# MelansonTech_Isolated_Shunt_Amplifier.net
KiCad netlist of a schematic drawn in Altium Designer
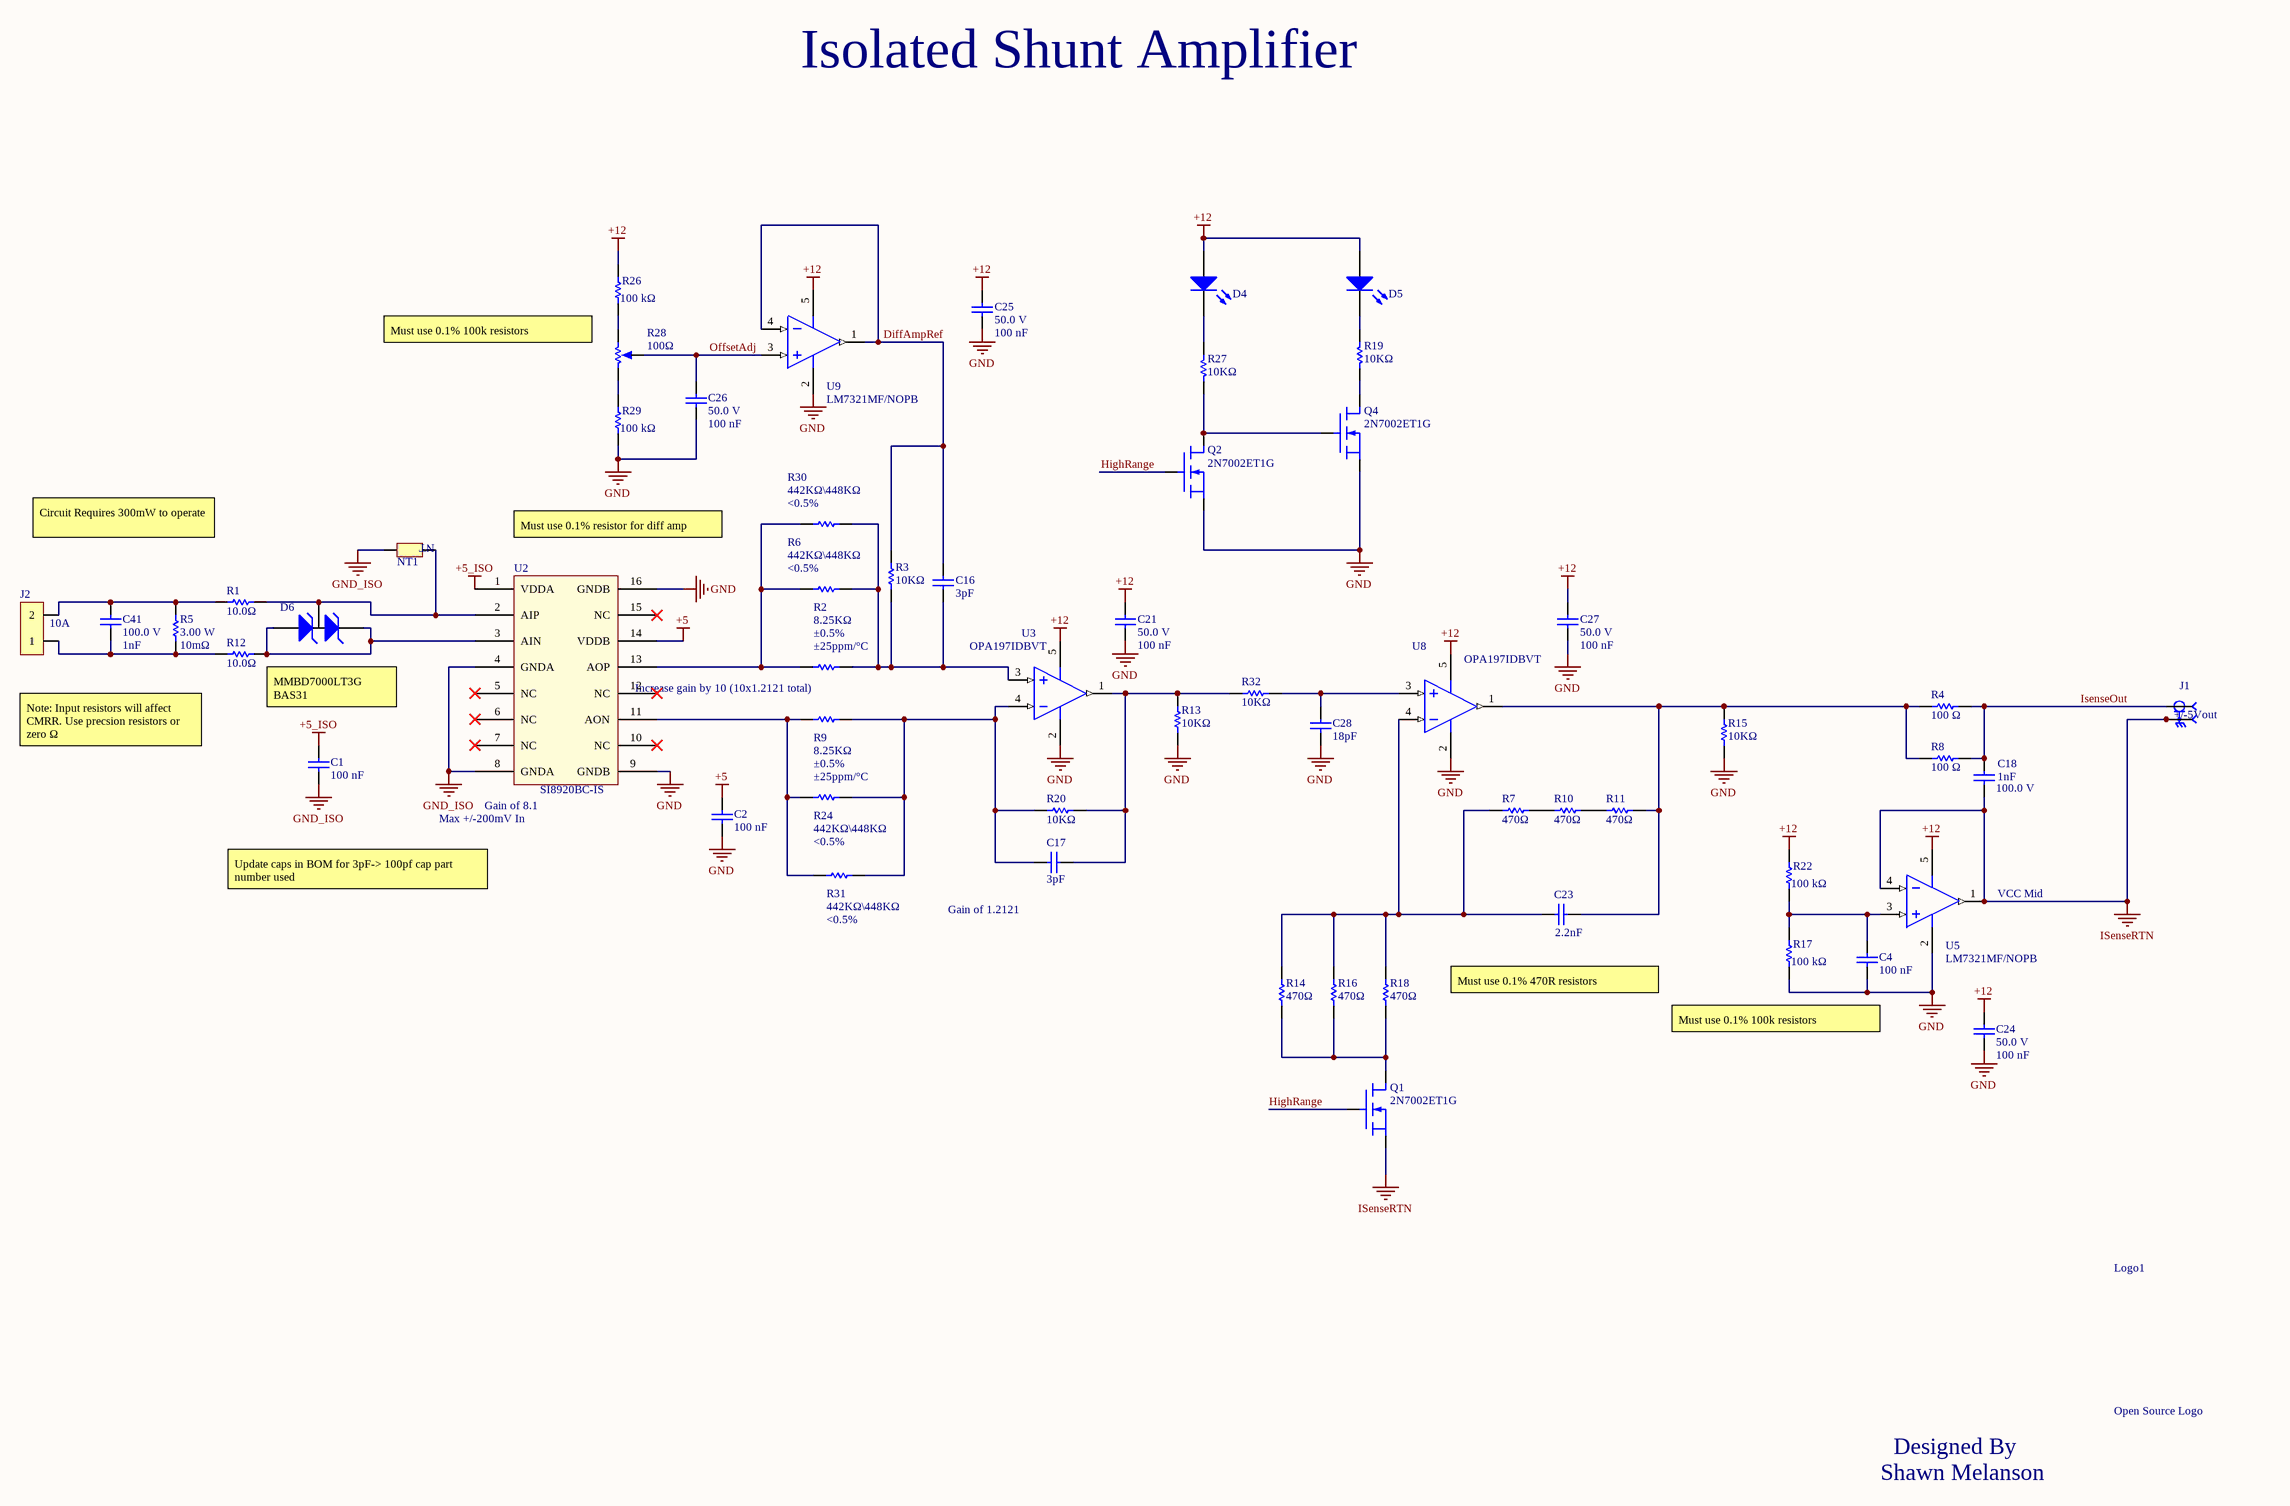
[diagram p0: MelansonTech Isolated Shunt Amplifier.SchDoc]

(export (version "E")
  (design (tool "Eeschema 10.0.6"))
  (components
    (comp (ref "C1")
      (value "08055C104JAT2A")
      (footprint "CAP, 0805, HD")
      (description "Capacitor; Ceramic; Cap 0.1 uF; Tol 5%; Vol-Rtg 50 VDC; SMT; 0805; X7R; Tape & Reel")
      (fields (field (name "CAPACITANCE") "100 nF"))
      (libsource (lib "Master Oct28_2018") (part "Cap,0805,100nf,50V,5%,08055C104JAT2A"))
    )
    (comp (ref "C2")
      (value "08055C104JAT2A")
      (footprint "CAP, 0805, HD")
      (description "Capacitor; Ceramic; Cap 0.1 uF; Tol 5%; Vol-Rtg 50 VDC; SMT; 0805; X7R; Tape & Reel")
      (fields (field (name "CAPACITANCE") "100 nF"))
      (libsource (lib "Master Oct28_2018") (part "Cap,0805,100nf,50V,5%,08055C104JAT2A"))
    )
    (comp (ref "C4")
      (value "08055C104JAT2A")
      (footprint "CAP, 0805, HD")
      (description "Capacitor; Ceramic; Cap 0.1 uF; Tol 5%; Vol-Rtg 50 VDC; SMT; 0805; X7R; Tape & Reel")
      (fields (field (name "CAPACITANCE") "100 nF"))
      (libsource (lib "Master Oct28_2018") (part "Cap,0805,100nf,50V,5%,08055C104JAT2A"))
    )
    (comp (ref "C16")
      (value "GRM21A5C2E101JW01D")
      (footprint "CAP, 0805, HD")
      (fields (field (name "CAPACITANCE") "3pF"))
      (libsource (lib "Master Nov2021") (part "CAP,0805,Generic"))
    )
    (comp (ref "C17")
      (value "GRM21A5C2E101JW01D")
      (footprint "CAP, 0805, HD")
      (fields (field (name "CAPACITANCE") "3pF"))
      (libsource (lib "Master Nov2021") (part "CAP,0805,Generic"))
    )
    (comp (ref "C18")
      (value "C0805X102J1GACAUTO")
      (footprint "CAP, 0805, HD")
      (description "CAPACITOR, 1NF, 100V, NP0, 0805")
      (fields (field (name "VOLTAGE RATING (DC)") "100.0 V") (field (name "CAPACITANCE") "1nF"))
      (libsource (lib "Master Nov2021") (part "Cap,0805,1nF,±5%,100Vdc,CL10F104ZB8NNNC"))
    )
    (comp (ref "C21")
      (value "08055C104JAT2A")
      (footprint "CAP, 0805, HD")
      (description "Capacitor; Ceramic; Cap 0.1 uF; Tol 5%; Vol-Rtg 50 VDC; SMT; 0805; X7R; Tape & Reel")
      (fields (field (name "VOLTAGE RATING (DC)") "50.0 V") (field (name "CAPACITANCE") "100 nF"))
      (libsource (lib "Master Mar2021") (part "Cap,0805,100nf,50V,5%,08055C104JAT2A"))
    )
    (comp (ref "C23")
      (value "Cap")
      (footprint "CAP, 0805, HD")
      (fields (field (name "CAP") "2.2nF"))
      (libsource (lib "Master Nov2021") (part "CAP,0805,Generic"))
    )
    (comp (ref "C24")
      (value "08055C104JAT2A")
      (footprint "CAP, 0805, HD")
      (description "Capacitor; Ceramic; Cap 0.1 uF; Tol 5%; Vol-Rtg 50 VDC; SMT; 0805; X7R; Tape & Reel")
      (fields (field (name "VOLTAGE RATING (DC)") "50.0 V") (field (name "CAPACITANCE") "100 nF"))
      (libsource (lib "Master Mar2021") (part "Cap,0805,100nf,50V,5%,08055C104JAT2A"))
    )
    (comp (ref "C25")
      (value "08055C104JAT2A")
      (footprint "CAP, 0805, HD")
      (description "Capacitor; Ceramic; Cap 0.1 uF; Tol 5%; Vol-Rtg 50 VDC; SMT; 0805; X7R; Tape & Reel")
      (fields (field (name "VOLTAGE RATING (DC)") "50.0 V") (field (name "CAPACITANCE") "100 nF"))
      (libsource (lib "Master Mar2021") (part "Cap,0805,100nf,50V,5%,08055C104JAT2A"))
    )
    (comp (ref "C26")
      (value "08055C104JAT2A")
      (footprint "CAP, 0805, HD")
      (description "Capacitor; Ceramic; Cap 0.1 uF; Tol 5%; Vol-Rtg 50 VDC; SMT; 0805; X7R; Tape & Reel")
      (fields (field (name "VOLTAGE RATING (DC)") "50.0 V") (field (name "CAPACITANCE") "100 nF"))
      (libsource (lib "Master Mar2021") (part "Cap,0805,100nf,50V,5%,08055C104JAT2A"))
    )
    (comp (ref "C27")
      (value "08055C104JAT2A")
      (footprint "CAP, 0805, HD")
      (description "Capacitor; Ceramic; Cap 0.1 uF; Tol 5%; Vol-Rtg 50 VDC; SMT; 0805; X7R; Tape & Reel")
      (fields (field (name "VOLTAGE RATING (DC)") "50.0 V") (field (name "CAPACITANCE") "100 nF"))
      (libsource (lib "Master Mar2021") (part "Cap,0805,100nf,50V,5%,08055C104JAT2A"))
    )
    (comp (ref "C28")
      (value "GRM21A5C2E101JW01D")
      (footprint "CAP, 0805, HD")
      (fields (field (name "CAPACITANCE") "18pF"))
      (libsource (lib "Master Nov2021") (part "CAP,0805,Generic"))
    )
    (comp (ref "C41")
      (value "C0805X102J1GACAUTO")
      (footprint "CAP, 0805, HD")
      (description "CAPACITOR, 1NF, 100V, NP0, 0805")
      (fields (field (name "VOLTAGE RATING (DC)") "100.0 V") (field (name "CAPACITANCE") "1nF"))
      (libsource (lib "Master Nov2021") (part "Cap,0805,1nF,±5%,100Vdc,CL10F104ZB8NNNC"))
    )
    (comp (ref "D4")
      (value "OVLBB4C7")
      (footprint "LED,TH,T1,3MM-Vert")
      (description "Blue 470nm LED Indication - Discrete 3.2V Radial")
      (fields (field (name "MFG") "TT Electronics/Optek Technology"))
      (libsource (lib "Master Nov2021") (part "LED,TH,T1,3mm,Blue,OVLBB4C7"))
    )
    (comp (ref "D5")
      (value "OVLBB4C7")
      (footprint "LED,TH,T1,3MM-Vert")
      (description "Blue 470nm LED Indication - Discrete 3.2V Radial")
      (fields (field (name "MFG") "TT Electronics/Optek Technology"))
      (libsource (lib "Master Nov2021") (part "LED,TH,T1,3mm,Blue,OVLBB4C7"))
    )
    (comp (ref "D6")
      (value "BAT54SLT1G")
      (footprint "SOT23-3")
      (fields (field (name "BASE PART NUMBER") "BAT54SL") (field (name "MANUFACTURER") "ON Semiconductor"))
      (libsource (lib "Master Nov2021") (part "Diode,Shottky,Array,Series,30V,200mA,BAT54SLT1G"))
    )
    (comp (ref "J1")
      (value "142-0701-801")
      (footprint "CINCH_142-0701-801")
      (description "CONN SMA JACK STR 50OHM EDGE MNT")
      (fields (field (name "MANUFACTURER") "Cinch Connectivity Solutions Johnson"))
      (libsource (lib "Master JUL_2019-Shawn") (part "Conn,SMA,Female,End Launch,142-0701-801"))
    )
    (comp (ref "J2")
      (value "TE Connectivity 282836-2")
      (footprint "TERM BLOCK 2POS SIDE ENTRY 5MM")
      (description "Wire to Board 2 Position 5 mm Pitch 30-16 AWG Euro Style Terminal Block")
      (fields (field (name "MANUFACTURER PART NUMBER") "282836-2"))
      (libsource (lib "Master DEC 2020") (part "TERM BLOCK 2POS SIDE ENTRY 5MM, 282836-2"))
    )
    (comp (ref "Logo1")
      (value "Open Source Logo")
      (footprint "Symbol,Open Source - No Text")
      (description "Open Source Silk Screen Logo")
      (libsource (lib "Master Nov2021") (part "Symbol,Open Source"))
    )
    (comp (ref "NT1")
      (value "Net Tie,0.254mm")
      (footprint "0.254mm Net Tie")
      (libsource (lib "Master Mar2021") (part "Net Tie,0.254mm"))
    )
    (comp (ref "Q1")
      (value "2N7002ET1G")
      (footprint "SOT23-3")
      (description "Small Signal MOSFET, 60 V, 310 mA, Single, N-Channel, 3-Pin SOT-23, Pb-Free, Tape and Reel")
      (fields
        (field (name "MANUFACTURER") "ON Semiconductor")
        (field (name "MANUFACTURER PART NUMBER") "2N7002ET1G")
      )
      (libsource (lib "Master DEC 2020") (part "MOSFET,N-Channel,SOT23,0.25A,60V,2N7002ET1G"))
    )
    (comp (ref "Q2")
      (value "2N7002ET1G")
      (footprint "SOT23-3")
      (description "Small Signal MOSFET, 60 V, 310 mA, Single, N-Channel, 3-Pin SOT-23, Pb-Free, Tape and Reel")
      (fields
        (field (name "MANUFACTURER") "ON Semiconductor")
        (field (name "MANUFACTURER PART NUMBER") "2N7002ET1G")
      )
      (libsource (lib "Master DEC 2020") (part "MOSFET,N-Channel,SOT23,0.25A,60V,2N7002ET1G"))
    )
    (comp (ref "Q4")
      (value "2N7002ET1G")
      (footprint "SOT23-3")
      (description "Small Signal MOSFET, 60 V, 310 mA, Single, N-Channel, 3-Pin SOT-23, Pb-Free, Tape and Reel")
      (fields
        (field (name "MANUFACTURER") "ON Semiconductor")
        (field (name "MANUFACTURER PART NUMBER") "2N7002ET1G")
      )
      (libsource (lib "Master DEC 2020") (part "MOSFET,N-Channel,SOT23,0.25A,60V,2N7002ET1G"))
    )
    (comp (ref "R1")
      (value "Vishay CRCW08051K00JNEA")
      (footprint "res, 0805, HD")
      (description "RES 10 OHM 5% 1/8W 0805")
      (fields
        (field (name "MANUFACTURER") "Stackpole Electronics Inc")
        (field (name "TOLERANCE") "±5%")
        (field (name "RESISTANCE") "10.0Ω")
      )
      (libsource (lib "Master Nov2021") (part "Res,0805,10.0Ω,5%,±200ppm/°C,RMCF0805JT10R0"))
    )
    (comp (ref "R2")
      (value "RR1220P-8251-D-M")
      (footprint "res, 0805, HD")
      (description "RES SMD 8.25KOHM 0.5% 1/10W 0805")
      (fields
        (field (name "MANUFACTURER") "Susumu")
        (field (name "TOLERANCE") "±0.5%")
        (field (name "TEMPERATURE COEFFICIENT") "±25ppm/°C")
        (field (name "RESISTANCE") "8.25KΩ")
      )
      (libsource (lib "Master DEC 2020") (part "Res,0805,8.25KΩ,0.5%,±25ppm/°C,RR1220P-8251-D-M"))
    )
    (comp (ref "R3")
      (value "Vishay / Dale CRCW080510K0FKTA")
      (footprint "res, 0805, HD")
      (description "RES SMD 10K OHM 1% 1/8W 0805")
      (fields (field (name "RESISTANCE") "10KΩ"))
      (libsource (lib "Master DEC 2020") (part "Res,0805,10.0kΩ,1%,100 ppm,CRCW080510K0FKTA"))
    )
    (comp (ref "R4")
      (value "CRCW0805100RJNEAC")
      (footprint "res, 0805, HD")
      (description "RES 100 OHM 5% 1/8W 0805")
      (fields (field (name "TOLERANCE") "±5%") (field (name "RESISTANCE") "100 Ω"))
      (libsource (lib "Master DEC 2020") (part "Res,0805,100Ω,5%,±200ppm/°C"))
    )
    (comp (ref "R5")
      (value "Res1")
      (footprint "Res 2512")
      (description "Resistor; Metal Film; Res 0.01 Ohms; Pwr-Rtg 3 W; Tol 1%; SMT; 2512; Current Sense")
      (fields
        (field (name "MANUFACTURER PART NUMBER") "CRA2512-FZ-R010ELF")
        (field (name "POWER RATING") "3.00 W")
        (field (name "RESISTANCE") "10mΩ")
      )
      (libsource (lib "Master JULY2019") (part "Res,2512,10mΩ,3.00W,±1%,CRA2512-FZ-R010ELF"))
    )
    (comp (ref "R6")
      (value "~")
      (footprint "res, 0805, HD")
      (fields (field (name "RESISTANCE") "442KΩ\\448KΩ") (field (name "TOLERANCE") "<0.5%"))
      (libsource (lib "Master Nov2021") (part "Res,0805,Generic"))
    )
    (comp (ref "R7")
      (value "CR0805-JW-471ELF")
      (footprint "res, 0805, HD")
      (description "RES SMD 470 OHM 5% 1/8W 0805")
      (fields
        (field (name "MANUFACTURER") "Bourns Inc.")
        (field (name "TOLERANCE") "±5%")
        (field (name "RESISTANCE") "470Ω")
      )
      (libsource (lib "Master Nov2021") (part "res,0805,470Ω,5%,200ppm,CR0805-JW-471ELF"))
    )
    (comp (ref "R8")
      (value "CRCW0805100RJNEAC")
      (footprint "res, 0805, HD")
      (description "RES 100 OHM 5% 1/8W 0805")
      (fields (field (name "TOLERANCE") "±5%") (field (name "RESISTANCE") "100 Ω"))
      (libsource (lib "Master DEC 2020") (part "Res,0805,100Ω,5%,±200ppm/°C"))
    )
    (comp (ref "R9")
      (value "RR1220P-8251-D-M")
      (footprint "res, 0805, HD")
      (description "RES SMD 8.25KOHM 0.5% 1/10W 0805")
      (fields
        (field (name "MANUFACTURER") "Susumu")
        (field (name "TOLERANCE") "±0.5%")
        (field (name "TEMPERATURE COEFFICIENT") "±25ppm/°C")
        (field (name "RESISTANCE") "8.25KΩ")
      )
      (libsource (lib "Master DEC 2020") (part "Res,0805,8.25KΩ,0.5%,±25ppm/°C,RR1220P-8251-D-M"))
    )
    (comp (ref "R10")
      (value "CR0805-JW-471ELF")
      (footprint "res, 0805, HD")
      (description "RES SMD 470 OHM 5% 1/8W 0805")
      (fields
        (field (name "MANUFACTURER") "Bourns Inc.")
        (field (name "TOLERANCE") "±5%")
        (field (name "RESISTANCE") "470Ω")
      )
      (libsource (lib "Master Nov2021") (part "res,0805,470Ω,5%,200ppm,CR0805-JW-471ELF"))
    )
    (comp (ref "R11")
      (value "CR0805-JW-471ELF")
      (footprint "res, 0805, HD")
      (description "RES SMD 470 OHM 5% 1/8W 0805")
      (fields
        (field (name "MANUFACTURER") "Bourns Inc.")
        (field (name "TOLERANCE") "±5%")
        (field (name "RESISTANCE") "470Ω")
      )
      (libsource (lib "Master Nov2021") (part "res,0805,470Ω,5%,200ppm,CR0805-JW-471ELF"))
    )
    (comp (ref "R12")
      (value "Vishay / Dale CRCW080510K0FKTA")
      (footprint "res, 0805, HD")
      (description "RES 10 OHM 5% 1/8W 0805")
      (fields
        (field (name "MANUFACTURER") "Stackpole Electronics Inc")
        (field (name "TOLERANCE") "±5%")
        (field (name "RESISTANCE") "10.0Ω")
      )
      (libsource (lib "Master Nov2021") (part "Res,0805,10.0Ω,5%,±200ppm/°C,RMCF0805JT10R0"))
    )
    (comp (ref "R13")
      (value "Vishay / Dale CRCW080510K0FKTA")
      (footprint "res, 0805, HD")
      (description "RES SMD 10K OHM 1% 1/8W 0805")
      (fields (field (name "RESISTANCE") "10KΩ"))
      (libsource (lib "Master DEC 2020") (part "Res,0805,10.0kΩ,1%,100 ppm,CRCW080510K0FKTA"))
    )
    (comp (ref "R14")
      (value "CR0805-JW-471ELF")
      (footprint "res, 0805, HD")
      (description "RES SMD 470 OHM 5% 1/8W 0805")
      (fields
        (field (name "MANUFACTURER") "Bourns Inc.")
        (field (name "TOLERANCE") "±5%")
        (field (name "RESISTANCE") "470Ω")
      )
      (libsource (lib "Master Nov2021") (part "res,0805,470Ω,5%,200ppm,CR0805-JW-471ELF"))
    )
    (comp (ref "R15")
      (value "Vishay / Dale CRCW080510K0FKTA")
      (footprint "res, 0805, HD")
      (description "RES SMD 10K OHM 1% 1/8W 0805")
      (fields (field (name "RESISTANCE") "10KΩ"))
      (libsource (lib "Master JULY2019") (part "Res,0805,10.0kΩ,1%,100 ppm,CRCW080510K0FKTA"))
    )
    (comp (ref "R16")
      (value "CR0805-JW-471ELF")
      (footprint "res, 0805, HD")
      (description "RES SMD 470 OHM 5% 1/8W 0805")
      (fields
        (field (name "MANUFACTURER") "Bourns Inc.")
        (field (name "TOLERANCE") "±5%")
        (field (name "RESISTANCE") "470Ω")
      )
      (libsource (lib "Master Nov2021") (part "res,0805,470Ω,5%,200ppm,CR0805-JW-471ELF"))
    )
    (comp (ref "R17")
      (value "CRCW0805100KFKEA")
      (footprint "res, 0805, HD")
      (description "100 kOhms ±1% 0.125W, 1/8W Chip Resistor 0805 (2012 Metric) Thick Film")
      (fields (field (name "MANUFACTURER") "Vishay") (field (name "RESISTANCE") "100 kΩ"))
      (libsource (lib "Master Nov2021") (part "Res,0805,100kΩ,1%,100ppm,CRCW0805100KFKEA"))
    )
    (comp (ref "R18")
      (value "CR0805-JW-471ELF")
      (footprint "res, 0805, HD")
      (description "RES SMD 470 OHM 5% 1/8W 0805")
      (fields
        (field (name "MANUFACTURER") "Bourns Inc.")
        (field (name "TOLERANCE") "±5%")
        (field (name "RESISTANCE") "470Ω")
      )
      (libsource (lib "Master Nov2021") (part "res,0805,470Ω,5%,200ppm,CR0805-JW-471ELF"))
    )
    (comp (ref "R19")
      (value "Vishay / Dale CRCW080510K0FKTA")
      (footprint "res, 0805, HD")
      (description "RES SMD 10K OHM 1% 1/8W 0805")
      (fields (field (name "RESISTANCE") "10KΩ"))
      (libsource (lib "Master JULY2019") (part "Res,0805,10.0kΩ,1%,100 ppm,CRCW080510K0FKTA"))
    )
    (comp (ref "R20")
      (value "Vishay / Dale CRCW080510K0FKTA")
      (footprint "res, 0805, HD")
      (description "RES SMD 10K OHM 1% 1/8W 0805")
      (fields (field (name "RESISTANCE") "10KΩ"))
      (libsource (lib "Master Nov2021") (part "Res,0805,10.0kΩ,1%,100 ppm,CRCW080510K0FKTA"))
    )
    (comp (ref "R22")
      (value "CRCW0805100KFKEA")
      (footprint "res, 0805, HD")
      (description "100 kOhms ±1% 0.125W, 1/8W Chip Resistor 0805 (2012 Metric) Thick Film")
      (fields (field (name "MANUFACTURER") "Vishay") (field (name "RESISTANCE") "100 kΩ"))
      (libsource (lib "Master Nov2021") (part "Res,0805,100kΩ,1%,100ppm,CRCW0805100KFKEA"))
    )
    (comp (ref "R24")
      (value "~")
      (footprint "res, 0805, HD")
      (fields (field (name "RESISTANCE") "442KΩ\\448KΩ") (field (name "TOLERANCE") "<0.5%"))
      (libsource (lib "Master Nov2021") (part "Res,0805,Generic"))
    )
    (comp (ref "R26")
      (value "CRCW0805100KFKEA")
      (footprint "res, 0805, HD")
      (description "100 kOhms ±1% 0.125W, 1/8W Chip Resistor 0805 (2012 Metric) Thick Film")
      (fields (field (name "MANUFACTURER") "Vishay") (field (name "RESISTANCE") "100 kΩ"))
      (libsource (lib "Master Nov2021") (part "Res,0805,100kΩ,1%,100ppm,CRCW0805100KFKEA"))
    )
    (comp (ref "R27")
      (value "Vishay / Dale CRCW080510K0FKTA")
      (footprint "res, 0805, HD")
      (description "RES SMD 10K OHM 1% 1/8W 0805")
      (fields (field (name "RESISTANCE") "10KΩ"))
      (libsource (lib "Master JULY2019") (part "Res,0805,10.0kΩ,1%,100 ppm,CRCW080510K0FKTA"))
    )
    (comp (ref "R28")
      (value "TC33X-2-101E")
      (footprint "Res,SMD,POT,TC33 Series")
      (description "TRIMMER 100 OHM 0.1W J LEAD TOP")
      (fields
        (field (name "MANUFACTURER") "Bourns Inc.")
        (field (name "TOLERANCE") "±25%")
        (field (name "RESISTANCE") "100Ω")
      )
      (libsource (lib "Master Nov2021") (part "Res,POT,SMD,100Ω,0.1W, TC33X-2-101E"))
    )
    (comp (ref "R29")
      (value "CRCW0805100KFKEA")
      (footprint "res, 0805, HD")
      (description "100 kOhms ±1% 0.125W, 1/8W Chip Resistor 0805 (2012 Metric) Thick Film")
      (fields (field (name "MANUFACTURER") "Vishay") (field (name "RESISTANCE") "100 kΩ"))
      (libsource (lib "Master Nov2021") (part "Res,0805,100kΩ,1%,100ppm,CRCW0805100KFKEA"))
    )
    (comp (ref "R30")
      (value "~")
      (footprint "res, 0805, HD")
      (fields (field (name "RESISTANCE") "442KΩ\\448KΩ") (field (name "TOLERANCE") "<0.5%"))
      (libsource (lib "Master Nov2021") (part "Res,0805,Generic"))
    )
    (comp (ref "R31")
      (value "~")
      (footprint "res, 0805, HD")
      (fields (field (name "RESISTANCE") "442KΩ\\448KΩ") (field (name "TOLERANCE") "<0.5%"))
      (libsource (lib "Master Nov2021") (part "Res,0805,Generic"))
    )
    (comp (ref "R32")
      (value "Vishay / Dale CRCW080510K0FKTA")
      (footprint "res, 0805, HD")
      (description "RES SMD 10K OHM 1% 1/8W 0805")
      (fields (field (name "RESISTANCE") "10KΩ"))
      (libsource (lib "Master DEC 2020") (part "Res,0805,10.0kΩ,1%,100 ppm,CRCW080510K0FKTA"))
    )
    (comp (ref "U2")
      (value "SI8920BC-IS")
      (footprint "SOIC-16 - Wide")
      (description "Isolation IC Inverters, Power Supplies, UPS 16-SOIC")
      (fields (field (name "MFR") "Skyworks Solutions Inc."))
      (libsource (lib "Master Nov2021") (part "IC,CurrentSense,Isolated,8.1Gain,950Khz, SI8920BC-IS"))
    )
    (comp (ref "U3")
      (value "OPA197IDBVT")
      (footprint "SOT23-5")
      (description "General Purpose Amplifier 1 Circuit Rail-to-Rail SOT-23-5")
      (fields (field (name "MANUFACTURER") "Texas Instruments") (field (name "MFG P/N") "OPA197IDBVT"))
      (libsource (lib "Master JULY2019") (part "OPAMP, single, General Purpose,Rail-to-Rail,10MHz,SOT-23-5,OPA197IDBVT"))
    )
    (comp (ref "U5")
      (value "LM7321MF/NOPB")
      (footprint "SOT23-5")
      (libsource (lib "Master Nov2021") (part "OPAMP,20Mhz,MOSFET DRIVER,SOT23-5,LM7321MF"))
    )
    (comp (ref "U8")
      (value "OPA197IDBVT")
      (footprint "SOT23-5")
      (description "General Purpose Amplifier 1 Circuit Rail-to-Rail SOT-23-5")
      (fields (field (name "MANUFACTURER") "Texas Instruments") (field (name "MFG P/N") "OPA197IDBVT"))
      (libsource (lib "Master JULY2019") (part "OPAMP, single, General Purpose,Rail-to-Rail,10MHz,SOT-23-5,OPA197IDBVT"))
    )
    (comp (ref "U9")
      (value "LM7321MF/NOPB")
      (footprint "SOT23-5")
      (libsource (lib "Master Nov2021") (part "OPAMP,20Mhz,MOSFET DRIVER,SOT23-5,LM7321MF"))
    )
  )
  (nets
    (net (code "1") (name "+5") (class "Default")
      (node (ref "C2") (pin "2") (pinfunction "2_2") (pintype "passive"))
      (node (ref "U2") (pin "14") (pinfunction "VDDB_14") (pintype "passive"))
    )
    (net (code "2") (name "+5_ISO") (class "Default")
      (node (ref "C1") (pin "2") (pinfunction "2_2") (pintype "passive"))
      (node (ref "U2") (pin "1") (pinfunction "VDDA_1") (pintype "passive"))
    )
    (net (code "3") (name "+12") (class "Default")
      (node (ref "C21") (pin "2") (pinfunction "2_2") (pintype "passive"))
      (node (ref "C24") (pin "2") (pinfunction "2_2") (pintype "passive"))
      (node (ref "C25") (pin "2") (pinfunction "2_2") (pintype "passive"))
      (node (ref "C27") (pin "2") (pinfunction "2_2") (pintype "passive"))
      (node (ref "D4") (pin "1") (pinfunction "A_1") (pintype "passive"))
      (node (ref "D5") (pin "1") (pinfunction "A_1") (pintype "passive"))
      (node (ref "R22") (pin "2") (pinfunction "2_2") (pintype "passive"))
      (node (ref "R26") (pin "2") (pinfunction "2_2") (pintype "passive"))
      (node (ref "U3") (pin "5") (pinfunction "V+_5") (pintype "power_in"))
      (node (ref "U5") (pin "5") (pinfunction "V+_5") (pintype "power_in"))
      (node (ref "U8") (pin "5") (pinfunction "V+_5") (pintype "power_in"))
      (node (ref "U9") (pin "5") (pinfunction "V+_5") (pintype "power_in"))
    )
    (net (code "4") (name "/DiffAmpRef") (class "Default")
      (node (ref "C16") (pin "1") (pinfunction "1_1") (pintype "passive"))
      (node (ref "R3") (pin "1") (pinfunction "1_1") (pintype "passive"))
      (node (ref "U9") (pin "1") (pinfunction "OUT_1") (pintype "output"))
      (node (ref "U9") (pin "4") (pinfunction "IN-_4") (pintype "input"))
    )
    (net (code "5") (name "/HighRange") (class "Default")
      (node (ref "Q1") (pin "1") (pinfunction "G_1") (pintype "passive"))
      (node (ref "Q2") (pin "1") (pinfunction "G_1") (pintype "passive"))
    )
    (net (code "6") (name "/IsenseOut") (class "Default")
      (node (ref "C18") (pin "2") (pinfunction "2_2") (pintype "passive"))
      (node (ref "J1") (pin "1") (pinfunction "1_1") (pintype "passive"))
      (node (ref "R4") (pin "1") (pinfunction "1_1") (pintype "passive"))
      (node (ref "R8") (pin "1") (pinfunction "1_1") (pintype "passive"))
    )
    (net (code "7") (name "/OffsetAdj") (class "Default")
      (node (ref "C26") (pin "2") (pinfunction "2_2") (pintype "passive"))
      (node (ref "R28") (pin "2") (pinfunction "2_2") (pintype "passive"))
      (node (ref "U9") (pin "3") (pinfunction "IN+_3") (pintype "input"))
    )
    (net (code "8") (name "GND") (class "Default")
      (node (ref "C2") (pin "1") (pinfunction "1_1") (pintype "passive"))
      (node (ref "C21") (pin "1") (pinfunction "1_1") (pintype "passive"))
      (node (ref "C24") (pin "1") (pinfunction "1_1") (pintype "passive"))
      (node (ref "C25") (pin "1") (pinfunction "1_1") (pintype "passive"))
      (node (ref "C26") (pin "1") (pinfunction "1_1") (pintype "passive"))
      (node (ref "C27") (pin "1") (pinfunction "1_1") (pintype "passive"))
      (node (ref "C28") (pin "2") (pinfunction "2_2") (pintype "passive"))
      (node (ref "C4") (pin "1") (pinfunction "1_1") (pintype "passive"))
      (node (ref "Q2") (pin "2") (pinfunction "S_2") (pintype "passive"))
      (node (ref "Q4") (pin "2") (pinfunction "S_2") (pintype "passive"))
      (node (ref "R13") (pin "2") (pinfunction "2_2") (pintype "passive"))
      (node (ref "R15") (pin "1") (pinfunction "1_1") (pintype "passive"))
      (node (ref "R17") (pin "1") (pinfunction "1_1") (pintype "passive"))
      (node (ref "R29") (pin "1") (pinfunction "1_1") (pintype "passive"))
      (node (ref "U2") (pin "16") (pinfunction "GNDB_16") (pintype "passive"))
      (node (ref "U2") (pin "9") (pinfunction "GNDB_9") (pintype "passive"))
      (node (ref "U3") (pin "2") (pinfunction "V-_2") (pintype "power_in"))
      (node (ref "U5") (pin "2") (pinfunction "V-_2") (pintype "power_in"))
      (node (ref "U8") (pin "2") (pinfunction "V-_2") (pintype "power_in"))
      (node (ref "U9") (pin "2") (pinfunction "V-_2") (pintype "power_in"))
    )
    (net (code "9") (name "GND_ISO") (class "Default")
      (node (ref "C1") (pin "1") (pinfunction "1_1") (pintype "passive"))
      (node (ref "NT1") (pin "2") (pinfunction "2_2") (pintype "passive"))
      (node (ref "U2") (pin "4") (pinfunction "GNDA_4") (pintype "passive"))
      (node (ref "U2") (pin "8") (pinfunction "GNDA_8") (pintype "passive"))
    )
    (net (code "10") (name "ISenseRTN") (class "Default")
      (node (ref "C18") (pin "1") (pinfunction "1_1") (pintype "passive"))
      (node (ref "J1") (pin "S1") (pinfunction "2_S1") (pintype "passive"))
      (node (ref "J1") (pin "S2") (pinfunction "2_S2") (pintype "passive"))
      (node (ref "J1") (pin "S3") (pinfunction "2_S3") (pintype "passive"))
      (node (ref "J1") (pin "S4") (pinfunction "2_S4") (pintype "passive"))
      (node (ref "Q1") (pin "2") (pinfunction "S_2") (pintype "passive"))
      (node (ref "U5") (pin "1") (pinfunction "OUT_1") (pintype "output"))
      (node (ref "U5") (pin "4") (pinfunction "IN-_4") (pintype "input"))
    )
    (net (code "11") (name "Net-(C41-Pad1)") (class "Default")
      (node (ref "C41") (pin "1") (pinfunction "1_1") (pintype "passive"))
      (node (ref "J2") (pin "1") (pinfunction "1_1") (pintype "passive"))
      (node (ref "R12") (pin "2") (pinfunction "2_2") (pintype "passive"))
      (node (ref "R5") (pin "2") (pinfunction "2_2") (pintype "passive"))
    )
    (net (code "12") (name "Net-(C41-Pad2)") (class "Default")
      (node (ref "C41") (pin "2") (pinfunction "2_2") (pintype "passive"))
      (node (ref "J2") (pin "2") (pinfunction "2_2") (pintype "passive"))
      (node (ref "R1") (pin "2") (pinfunction "2_2") (pintype "passive"))
      (node (ref "R5") (pin "1") (pinfunction "1_1") (pintype "passive"))
    )
    (net (code "13") (name "Net-(D4-K)") (class "Default")
      (node (ref "D4") (pin "2") (pinfunction "K_2") (pintype "passive"))
      (node (ref "R27") (pin "1") (pinfunction "1_1") (pintype "passive"))
    )
    (net (code "14") (name "Net-(D5-K)") (class "Default")
      (node (ref "D5") (pin "2") (pinfunction "K_2") (pintype "passive"))
      (node (ref "R19") (pin "1") (pinfunction "1_1") (pintype "passive"))
    )
    (net (code "15") (name "Net-(D6-A)") (class "Default")
      (node (ref "D6") (pin "1") (pinfunction "A_1") (pintype "passive"))
      (node (ref "D6") (pin "2") (pinfunction "K_2") (pintype "passive"))
      (node (ref "R12") (pin "1") (pinfunction "1_1") (pintype "passive"))
      (node (ref "U2") (pin "3") (pinfunction "AIN_3") (pintype "passive"))
    )
    (net (code "16") (name "Net-(D6-AK)") (class "Default")
      (node (ref "D6") (pin "3") (pinfunction "AK_3") (pintype "passive"))
      (node (ref "NT1") (pin "1") (pinfunction "1_1") (pintype "passive"))
      (node (ref "R1") (pin "1") (pinfunction "1_1") (pintype "passive"))
      (node (ref "U2") (pin "2") (pinfunction "AIP_2") (pintype "passive"))
    )
    (net (code "17") (name "Net-(Q1-D)") (class "Default")
      (node (ref "Q1") (pin "3") (pinfunction "D_3") (pintype "passive"))
      (node (ref "R14") (pin "2") (pinfunction "2_2") (pintype "passive"))
      (node (ref "R16") (pin "2") (pinfunction "2_2") (pintype "passive"))
      (node (ref "R18") (pin "2") (pinfunction "2_2") (pintype "passive"))
    )
    (net (code "18") (name "Net-(Q2-D)") (class "Default")
      (node (ref "Q2") (pin "3") (pinfunction "D_3") (pintype "passive"))
      (node (ref "Q4") (pin "1") (pinfunction "G_1") (pintype "passive"))
      (node (ref "R27") (pin "2") (pinfunction "2_2") (pintype "passive"))
    )
    (net (code "19") (name "Net-(Q4-D)") (class "Default")
      (node (ref "Q4") (pin "3") (pinfunction "D_3") (pintype "passive"))
      (node (ref "R19") (pin "2") (pinfunction "2_2") (pintype "passive"))
    )
    (net (code "20") (name "Net-(R10-Pad1)") (class "Default")
      (node (ref "R10") (pin "1") (pinfunction "1_1") (pintype "passive"))
      (node (ref "R11") (pin "2") (pinfunction "2_2") (pintype "passive"))
    )
    (net (code "21") (name "Net-(R10-Pad2)") (class "Default")
      (node (ref "R10") (pin "2") (pinfunction "2_2") (pintype "passive"))
      (node (ref "R7") (pin "1") (pinfunction "1_1") (pintype "passive"))
    )
    (net (code "22") (name "Net-(R26-Pad1)") (class "Default")
      (node (ref "R26") (pin "1") (pinfunction "1_1") (pintype "passive"))
      (node (ref "R28") (pin "3") (pinfunction "3_3") (pintype "passive"))
    )
    (net (code "23") (name "Net-(R28-Pad1)") (class "Default")
      (node (ref "R28") (pin "1") (pinfunction "1_1") (pintype "passive"))
      (node (ref "R29") (pin "2") (pinfunction "2_2") (pintype "passive"))
    )
    (net (code "24") (name "Net-(U2-AON)") (class "Default")
      (node (ref "R24") (pin "2") (pinfunction "2_2") (pintype "passive"))
      (node (ref "R31") (pin "2") (pinfunction "2_2") (pintype "passive"))
      (node (ref "R9") (pin "2") (pinfunction "2_2") (pintype "passive"))
      (node (ref "U2") (pin "11") (pinfunction "AON_11") (pintype "passive"))
    )
    (net (code "25") (name "Net-(U2-AOP)") (class "Default")
      (node (ref "R2") (pin "2") (pinfunction "2_2") (pintype "passive"))
      (node (ref "R30") (pin "2") (pinfunction "2_2") (pintype "passive"))
      (node (ref "R6") (pin "2") (pinfunction "2_2") (pintype "passive"))
      (node (ref "U2") (pin "13") (pinfunction "AOP_13") (pintype "passive"))
    )
    (net (code "26") (name "Net-(U3-1IN+)") (class "Default")
      (node (ref "C16") (pin "2") (pinfunction "2_2") (pintype "passive"))
      (node (ref "R2") (pin "1") (pinfunction "1_1") (pintype "passive"))
      (node (ref "R3") (pin "2") (pinfunction "2_2") (pintype "passive"))
      (node (ref "R30") (pin "1") (pinfunction "1_1") (pintype "passive"))
      (node (ref "R6") (pin "1") (pinfunction "1_1") (pintype "passive"))
      (node (ref "U3") (pin "3") (pinfunction "1IN+_3") (pintype "input"))
    )
    (net (code "27") (name "Net-(U3-1IN-)") (class "Default")
      (node (ref "C17") (pin "2") (pinfunction "2_2") (pintype "passive"))
      (node (ref "R20") (pin "2") (pinfunction "2_2") (pintype "passive"))
      (node (ref "R24") (pin "1") (pinfunction "1_1") (pintype "passive"))
      (node (ref "R31") (pin "1") (pinfunction "1_1") (pintype "passive"))
      (node (ref "R9") (pin "1") (pinfunction "1_1") (pintype "passive"))
      (node (ref "U3") (pin "4") (pinfunction "1IN-_4") (pintype "input"))
    )
    (net (code "28") (name "Net-(U3-1OUT)") (class "Default")
      (node (ref "C17") (pin "1") (pinfunction "1_1") (pintype "passive"))
      (node (ref "R13") (pin "1") (pinfunction "1_1") (pintype "passive"))
      (node (ref "R20") (pin "1") (pinfunction "1_1") (pintype "passive"))
      (node (ref "R32") (pin "1") (pinfunction "1_1") (pintype "passive"))
      (node (ref "U3") (pin "1") (pinfunction "1OUT_1") (pintype "output"))
    )
    (net (code "29") (name "Net-(U5-IN+)") (class "Default")
      (node (ref "C4") (pin "2") (pinfunction "2_2") (pintype "passive"))
      (node (ref "R17") (pin "2") (pinfunction "2_2") (pintype "passive"))
      (node (ref "R22") (pin "1") (pinfunction "1_1") (pintype "passive"))
      (node (ref "U5") (pin "3") (pinfunction "IN+_3") (pintype "input"))
    )
    (net (code "30") (name "Net-(U8-1IN+)") (class "Default")
      (node (ref "C28") (pin "1") (pinfunction "1_1") (pintype "passive"))
      (node (ref "R32") (pin "2") (pinfunction "2_2") (pintype "passive"))
      (node (ref "U8") (pin "3") (pinfunction "1IN+_3") (pintype "input"))
    )
    (net (code "31") (name "Net-(U8-1IN-)") (class "Default")
      (node (ref "C23") (pin "2") (pinfunction "2_2") (pintype "passive"))
      (node (ref "R14") (pin "1") (pinfunction "1_1") (pintype "passive"))
      (node (ref "R16") (pin "1") (pinfunction "1_1") (pintype "passive"))
      (node (ref "R18") (pin "1") (pinfunction "1_1") (pintype "passive"))
      (node (ref "R7") (pin "2") (pinfunction "2_2") (pintype "passive"))
      (node (ref "U8") (pin "4") (pinfunction "1IN-_4") (pintype "input"))
    )
    (net (code "32") (name "Net-(U8-1OUT)") (class "Default")
      (node (ref "C23") (pin "1") (pinfunction "1_1") (pintype "passive"))
      (node (ref "R11") (pin "1") (pinfunction "1_1") (pintype "passive"))
      (node (ref "R15") (pin "2") (pinfunction "2_2") (pintype "passive"))
      (node (ref "R4") (pin "2") (pinfunction "2_2") (pintype "passive"))
      (node (ref "R8") (pin "2") (pinfunction "2_2") (pintype "passive"))
      (node (ref "U8") (pin "1") (pinfunction "1OUT_1") (pintype "output"))
    )
    (net (code "33") (name "unconnected-(U2-NC-Pad5)") (class "Default")
      (node (ref "U2") (pin "5") (pinfunction "NC_5") (pintype "passive+no_connect"))
    )
    (net (code "34") (name "unconnected-(U2-NC-Pad6)") (class "Default")
      (node (ref "U2") (pin "6") (pinfunction "NC_6") (pintype "passive+no_connect"))
    )
    (net (code "35") (name "unconnected-(U2-NC-Pad7)") (class "Default")
      (node (ref "U2") (pin "7") (pinfunction "NC_7") (pintype "passive+no_connect"))
    )
    (net (code "36") (name "unconnected-(U2-NC-Pad10)") (class "Default")
      (node (ref "U2") (pin "10") (pinfunction "NC_10") (pintype "passive+no_connect"))
    )
    (net (code "37") (name "unconnected-(U2-NC-Pad12)") (class "Default")
      (node (ref "U2") (pin "12") (pinfunction "NC_12") (pintype "passive+no_connect"))
    )
    (net (code "38") (name "unconnected-(U2-NC-Pad15)") (class "Default")
      (node (ref "U2") (pin "15") (pinfunction "NC_15") (pintype "passive+no_connect"))
    )
  )
)
